# Sheet1_2.net
KiCad netlist of a schematic drawn in Altium Designer
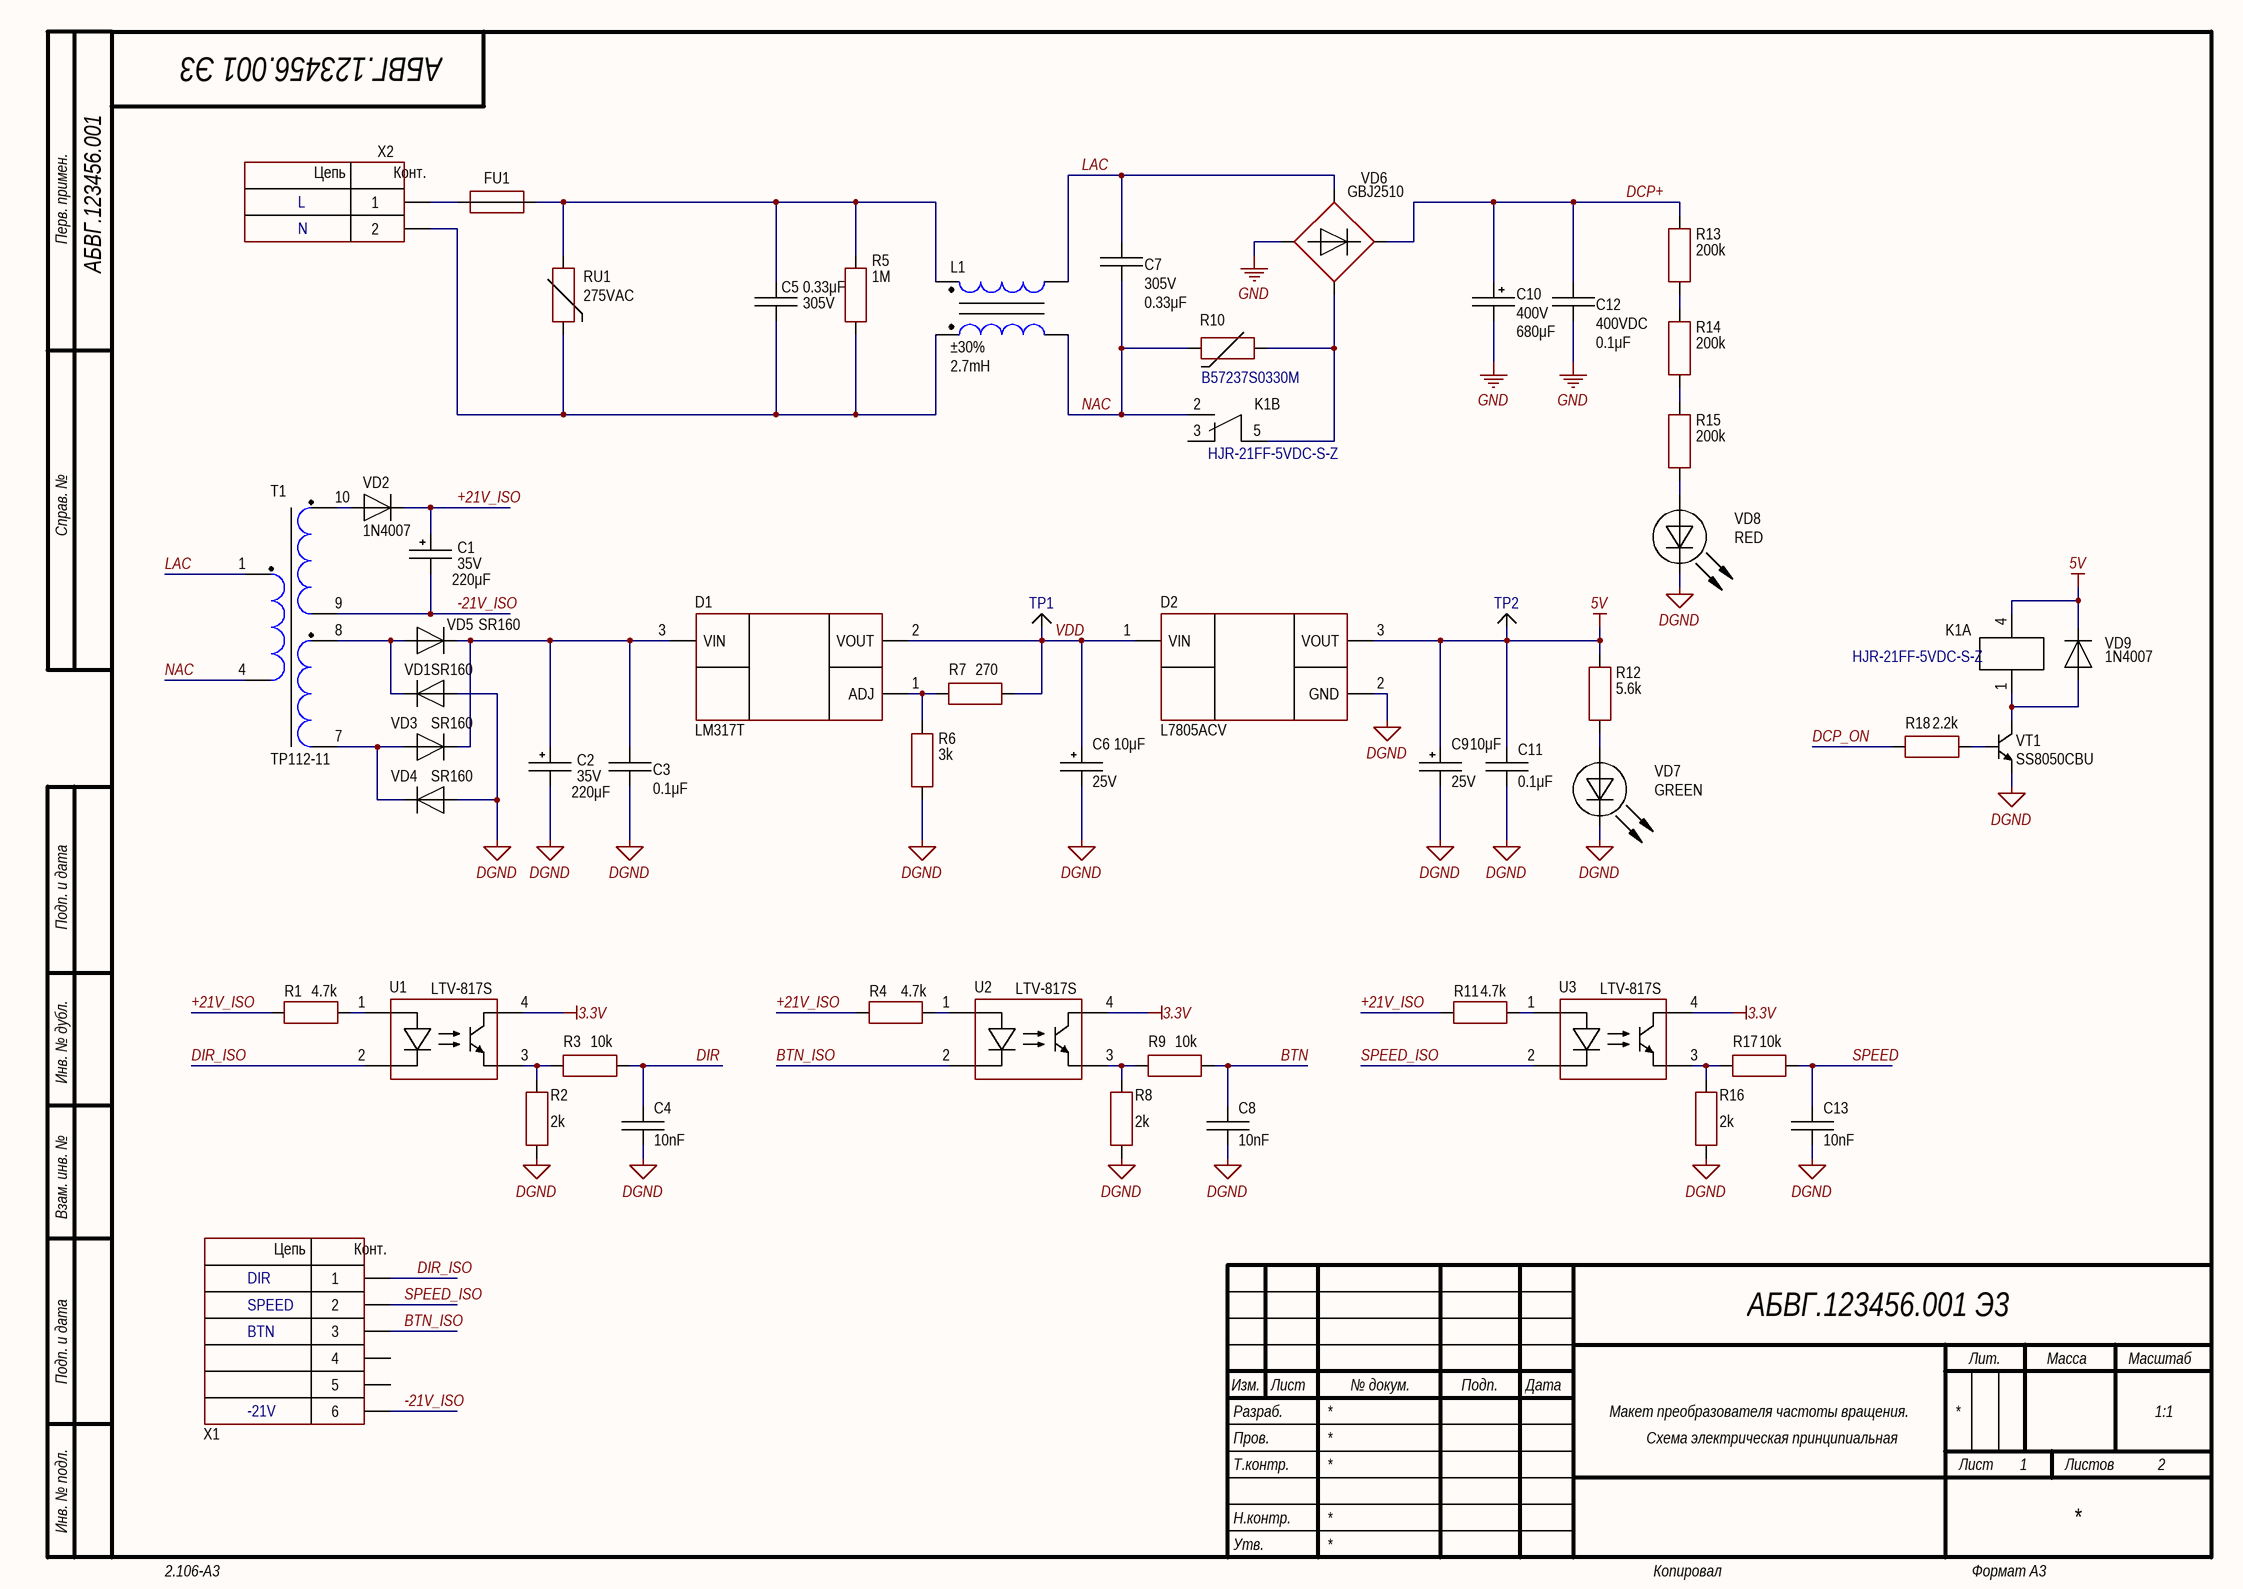
[diagram p0: Sheet1 (2).SchDoc]

(export (version "E")
  (design (tool "Eeschema 10.0.6"))
  (components
    (comp (ref "C1")
      (value "220μF")
      (footprint "CAP: D8C3.5H12")
      (fields
        (field (name "MANUFACTURER") "?")
        (field (name "PARTNUMBER") "9000565901")
        (field (name "VALUEMANUFACTURERPARTNUMBER") "Aluminium capacitor, 220μF, 35V, ±20%, 54mOhm, 8x12x3.5 mm, -40...+105°C")
        (field (name "VOLTAGE") "35V")
      )
      (libsource (lib "capacitor") (part "Aluminium"))
    )
    (comp (ref "C2")
      (value "220μF")
      (footprint "CAP: D8C3.5H12")
      (fields
        (field (name "MANUFACTURER") "?")
        (field (name "PARTNUMBER") "9000565901")
        (field (name "VALUEMANUFACTURERPARTNUMBER") "Aluminium capacitor, 220μF, 35V, ±20%, 54mOhm, 8x12x3.5 mm, -40...+105°C")
        (field (name "VOLTAGE") "35V")
      )
      (libsource (lib "capacitor") (part "Aluminium"))
    )
    (comp (ref "C3")
      (value "0.1μF")
      (footprint "CAP: 1206")
      (fields
        (field (name "PARTNUMBER") "Ceramic capacitor, 0.1μF,   50V")
        (field (name "VALUEMANUFACTURERPARTNUMBER") "Ceramic capacitor, 0.1μF, X7R, ±10%, 50V, 1206, -55...+125°C")
        (field (name "TOLERANCE") "±10%")
      )
      (libsource (lib "capacitor") (part "Ceramic_1206"))
    )
    (comp (ref "C4")
      (value "10nF")
      (footprint "CAP: 1206")
      (fields
        (field (name "PARTNUMBER") "Ceramic capacitor, 10nF,   50V")
        (field (name "VALUEMANUFACTURERPARTNUMBER") "Ceramic capacitor, 10nF, X7R, ±10%, 50V, 1206, -55...+125°C")
        (field (name "TOLERANCE") "±10%")
      )
      (libsource (lib "capacitor") (part "Ceramic_1206"))
    )
    (comp (ref "C5")
      (value "0.33μF")
      (footprint "CAP: B32922")
      (fields
        (field (name "MANUFACTURER") "Epcos")
        (field (name "PARTNUMBER") "B32922-C3334-K")
        (field (name "VALUEMANUFACTURERPARTNUMBER") "Film capacitor X2, 0.33μF, 305V, ±10%, ?, 18x14x8, -40...+110°C")
        (field (name "VOLTAGE") "305V")
      )
      (libsource (lib "capacitor") (part "Film"))
    )
    (comp (ref "C6")
      (value "10μF")
      (footprint "CAP: D5C2H11")
      (fields
        (field (name "MANUFACTURER") "?")
        (field (name "PARTNUMBER") "9000565842")
        (field (name "VALUEMANUFACTURERPARTNUMBER") "Aluminium capacitor, 10μF, 25V, ±20%, 54mOhm, ?, -40...+105°C")
        (field (name "VOLTAGE") "25V")
      )
      (libsource (lib "capacitor") (part "Aluminium"))
    )
    (comp (ref "C7")
      (value "0.33μF")
      (footprint "CAP: B32922")
      (fields
        (field (name "MANUFACTURER") "Epcos")
        (field (name "PARTNUMBER") "B32922-C3334-K")
        (field (name "VALUEMANUFACTURERPARTNUMBER") "Film capacitor X2, 0.33μF, 305V, ±10%, ?, 18x14x8, -40...+110°C")
        (field (name "VOLTAGE") "305V")
      )
      (libsource (lib "capacitor") (part "Film"))
    )
    (comp (ref "C8")
      (value "10nF")
      (footprint "CAP: 1206")
      (fields
        (field (name "PARTNUMBER") "Ceramic capacitor, 10nF,   50V")
        (field (name "VALUEMANUFACTURERPARTNUMBER") "Ceramic capacitor, 10nF, X7R, ±10%, 50V, 1206, -55...+125°C")
        (field (name "TOLERANCE") "±10%")
      )
      (libsource (lib "capacitor") (part "Ceramic_1206"))
    )
    (comp (ref "C9")
      (value "10μF")
      (footprint "CAP: D5C2H11")
      (fields
        (field (name "MANUFACTURER") "?")
        (field (name "PARTNUMBER") "9000565842")
        (field (name "VALUEMANUFACTURERPARTNUMBER") "Aluminium capacitor, 10μF, 25V, ±20%, 54mOhm, ?, -40...+105°C")
        (field (name "VOLTAGE") "25V")
      )
      (libsource (lib "capacitor") (part "Aluminium"))
    )
    (comp (ref "C10")
      (value "680μF")
      (footprint "CAP: D30C10H37")
      (fields
        (field (name "MANUFACTURER") "JB Capacitors")
        (field (name "PARTNUMBER") "JNE2G681M10003000600")
        (field (name "VALUEMANUFACTURERPARTNUMBER") "Aluminium capacitor, 680μF, 400V, ±20%, ?, 30x10x60 mm, -25...+105°C")
        (field (name "VOLTAGE") "400V")
      )
      (libsource (lib "capacitor") (part "Aluminium"))
    )
    (comp (ref "C11")
      (value "0.1μF")
      (footprint "CAP: 1206")
      (fields
        (field (name "PARTNUMBER") "Ceramic capacitor, 0.1μF,   50V")
        (field (name "VALUEMANUFACTURERPARTNUMBER") "Ceramic capacitor, 0.1μF, X7R, ±10%, 50V, 1206, -55...+125°C")
        (field (name "TOLERANCE") "±10%")
      )
      (libsource (lib "capacitor") (part "Ceramic_1206"))
    )
    (comp (ref "C12")
      (value "0.1μF")
      (footprint "CAP: B32673")
      (fields
        (field (name "MANUFACTURER") "Epcos")
        (field (name "PARTNUMBER") "B32683A4104J000")
        (field (name "VALUEMANUFACTURERPARTNUMBER") "Film capacitor, 0.1μF, 400VDC, ±10%, ?, 26.5x16.5x8.5 mm, -55...+100°C")
        (field (name "VOLTAGE") "400VDC")
      )
      (libsource (lib "capacitor") (part "Film"))
    )
    (comp (ref "C13")
      (value "10nF")
      (footprint "CAP: 1206")
      (fields
        (field (name "PARTNUMBER") "Ceramic capacitor, 10nF,   50V")
        (field (name "VALUEMANUFACTURERPARTNUMBER") "Ceramic capacitor, 10nF, X7R, ±10%, 50V, 1206, -55...+125°C")
        (field (name "TOLERANCE") "±10%")
      )
      (libsource (lib "capacitor") (part "Ceramic_1206"))
    )
    (comp (ref "D1")
      (value "~")
      (footprint "TO-220F")
      (description "Adjustable voltage regulator")
      (fields
        (field (name "MANUFACTURER") "STMicroelectronics")
        (field (name "VALUEMANUFACTURERPARTNUMBER") ", , , , , , , TO-220SG, 0...125°C")
        (field (name "PARTNUMBER") "LM317T")
      )
      (libsource (lib "ic-power-supply") (part "LM317"))
    )
    (comp (ref "D2")
      (value "~")
      (footprint "TO-220F")
      (description "Linear voltage regulator")
      (fields
        (field (name "MANUFACTURER") "STMicroelectronics")
        (field (name "VALUEMANUFACTURERPARTNUMBER") ", , , , , , , *, *")
        (field (name "PARTNUMBER") "L7805ACV")
      )
      (libsource (lib "ic-power-supply") (part "78XX"))
    )
    (comp (ref "FU1")
      (value "~")
      (footprint "FUSE: FH-101")
      (fields
        (field (name "MANUFACTURER") "Dragon City Industries")
        (field (name "PARTNUMBER") "FH-101")
        (field (name "VALUEMANUFACTURERPARTNUMBER") "*,  FH-101, *")
      )
      (libsource (lib "resistor") (part "FUSE"))
    )
    (comp (ref "K1")
      (value "Relay, Non Latching, SPDT , 10A , (250VAC , 110VDC)")
      (footprint "HJR-21FF-5VDC-S-Z")
      (fields (field (name "MANUFACTURER") "Tianbo") (field (name "PARTNUMBER") "HJR-21FF-5VDC-S-Z"))
      (libsource (lib "relay") (part "HJR-21FF-5VDC-S-Z"))
    )
    (comp (ref "L1")
      (value "2.7mH")
      (footprint "IND: B82723A")
      (fields
        (field (name "MANUFACTURER") "TDK (TDK-Lambda)")
        (field (name "PARTNUMBER") "B82723A2402N1")
        (field (name "VALUEMANUFACTURERPARTNUMBER") "Fixed inductor, 2.7mH, ±30%, B82723A, CuNi18Zn20, ")
        (field (name "TOLERANCE") "±30%")
      )
      (libsource (lib "inductor") (part "B82723A"))
    )
    (comp (ref "R1")
      (value "4.7k")
      (footprint "RES: 1206")
      (fields
        (field (name "MANUFACTURER") "Yageo")
        (field (name "PARTNUMBER") "RC1206JR-07100RL")
        (field (name "VALUEMANUFACTURERPARTNUMBER") "Resistor film, 4.7k, ±5%, 1206, 0.25W, -55...+125°C")
      )
      (libsource (lib "") (part "Resistor_1206_2"))
    )
    (comp (ref "R2")
      (value "2k")
      (footprint "RES: 1206")
      (fields
        (field (name "MANUFACTURER") "Yageo")
        (field (name "PARTNUMBER") "RC1206JR-07100RL")
        (field (name "VALUEMANUFACTURERPARTNUMBER") "Resistor film, 2k, ±5%, 1206, 0.25W, -55...+125°C")
      )
      (libsource (lib "resistor") (part "Resistor_1206"))
    )
    (comp (ref "R3")
      (value "10k")
      (footprint "RES: 1206")
      (fields
        (field (name "MANUFACTURER") "Yageo")
        (field (name "PARTNUMBER") "RC1206JR-07100RL")
        (field (name "VALUEMANUFACTURERPARTNUMBER") "Resistor film, 10k, ±5%, 1206, 0.25W, -55...+125°C")
      )
      (libsource (lib "") (part "Resistor_1206_1"))
    )
    (comp (ref "R4")
      (value "4.7k")
      (footprint "RES: 1206")
      (fields
        (field (name "MANUFACTURER") "Yageo")
        (field (name "PARTNUMBER") "RC1206JR-07100RL")
        (field (name "VALUEMANUFACTURERPARTNUMBER") "Resistor film, 4.7k, ±5%, 1206, 0.25W, -55...+125°C")
      )
      (libsource (lib "") (part "Resistor_1206_2"))
    )
    (comp (ref "R5")
      (value "1M")
      (footprint "RES: Axial 15mm")
      (fields (field (name "TOLERANCE") "±5%"))
      (libsource (lib "resistor") (part "Resistor_Axial"))
    )
    (comp (ref "R6")
      (value "3k")
      (footprint "RES: 1206")
      (fields
        (field (name "MANUFACTURER") "Yageo")
        (field (name "PARTNUMBER") "RC1206JR-07100RL")
        (field (name "VALUEMANUFACTURERPARTNUMBER") "Resistor film, 3k, ±5%, 1206, 0.25W, -55...+125°C")
      )
      (libsource (lib "resistor") (part "Resistor_1206"))
    )
    (comp (ref "R7")
      (value "270")
      (footprint "RES: 1206")
      (fields
        (field (name "MANUFACTURER") "Yageo")
        (field (name "PARTNUMBER") "RC1206JR-07100RL")
        (field (name "VALUEMANUFACTURERPARTNUMBER") "Resistor film, 270, ±5%, 1206, 0.25W, -55...+125°C")
      )
      (libsource (lib "") (part "Resistor_1206_2"))
    )
    (comp (ref "R8")
      (value "2k")
      (footprint "RES: 1206")
      (fields
        (field (name "MANUFACTURER") "Yageo")
        (field (name "PARTNUMBER") "RC1206JR-07100RL")
        (field (name "VALUEMANUFACTURERPARTNUMBER") "Resistor film, 2k, ±5%, 1206, 0.25W, -55...+125°C")
      )
      (libsource (lib "resistor") (part "Resistor_1206"))
    )
    (comp (ref "R9")
      (value "10k")
      (footprint "RES: 1206")
      (fields
        (field (name "MANUFACTURER") "Yageo")
        (field (name "PARTNUMBER") "RC1206JR-07100RL")
        (field (name "VALUEMANUFACTURERPARTNUMBER") "Resistor film, 10k, ±5%, 1206, 0.25W, -55...+125°C")
      )
      (libsource (lib "") (part "Resistor_1206_1"))
    )
    (comp (ref "R10")
      (value "~")
      (footprint "RES: B57237 (NTC)")
      (description "Maximum permissible capacitance 900uF")
      (fields
        (field (name "MANUFACTURER") "Epcos")
        (field (name "PARTNUMBER") "B57237S0330M")
        (field (name "VALUEMANUFACTURERPARTNUMBER") "NTC resistor, 33, ±20%, pitch 7.5mm, 2.5A, -55...+170°C")
      )
      (libsource (lib "resistor") (part "NTC"))
    )
    (comp (ref "R11")
      (value "4.7k")
      (footprint "RES: 1206")
      (fields
        (field (name "MANUFACTURER") "Yageo")
        (field (name "PARTNUMBER") "RC1206JR-07100RL")
        (field (name "VALUEMANUFACTURERPARTNUMBER") "Resistor film, 4.7k, ±5%, 1206, 0.25W, -55...+125°C")
      )
      (libsource (lib "") (part "Resistor_1206_2"))
    )
    (comp (ref "R12")
      (value "5.6k")
      (footprint "RES: 1206")
      (fields
        (field (name "MANUFACTURER") "Yageo")
        (field (name "PARTNUMBER") "RC1206JR-07100RL")
        (field (name "VALUEMANUFACTURERPARTNUMBER") "Resistor film, 5.6k, ±5%, 1206, 0.25W, -55...+125°C")
      )
      (libsource (lib "resistor") (part "Resistor_1206"))
    )
    (comp (ref "R13")
      (value "200k")
      (footprint "RES: 1206")
      (fields
        (field (name "MANUFACTURER") "Yageo")
        (field (name "PARTNUMBER") "RC1206JR-07100RL")
        (field (name "VALUEMANUFACTURERPARTNUMBER") "Resistor film, 200k, ±5%, 1206, 0.25W, -55...+125°C")
      )
      (libsource (lib "resistor") (part "Resistor_1206"))
    )
    (comp (ref "R14")
      (value "200k")
      (footprint "RES: 1206")
      (fields
        (field (name "MANUFACTURER") "Yageo")
        (field (name "PARTNUMBER") "RC1206JR-07100RL")
        (field (name "VALUEMANUFACTURERPARTNUMBER") "Resistor film, 200k, ±5%, 1206, 0.25W, -55...+125°C")
      )
      (libsource (lib "resistor") (part "Resistor_1206"))
    )
    (comp (ref "R15")
      (value "200k")
      (footprint "RES: 1206")
      (fields
        (field (name "MANUFACTURER") "Yageo")
        (field (name "PARTNUMBER") "RC1206JR-07100RL")
        (field (name "VALUEMANUFACTURERPARTNUMBER") "Resistor film, 200k, ±5%, 1206, 0.25W, -55...+125°C")
      )
      (libsource (lib "resistor") (part "Resistor_1206"))
    )
    (comp (ref "R16")
      (value "2k")
      (footprint "RES: 1206")
      (fields
        (field (name "MANUFACTURER") "Yageo")
        (field (name "PARTNUMBER") "RC1206JR-07100RL")
        (field (name "VALUEMANUFACTURERPARTNUMBER") "Resistor film, 2k, ±5%, 1206, 0.25W, -55...+125°C")
      )
      (libsource (lib "resistor") (part "Resistor_1206"))
    )
    (comp (ref "R17")
      (value "10k")
      (footprint "RES: 1206")
      (fields
        (field (name "MANUFACTURER") "Yageo")
        (field (name "PARTNUMBER") "RC1206JR-07100RL")
        (field (name "VALUEMANUFACTURERPARTNUMBER") "Resistor film, 10k, ±5%, 1206, 0.25W, -55...+125°C")
      )
      (libsource (lib "") (part "Resistor_1206_1"))
    )
    (comp (ref "R18")
      (value "2.2k")
      (footprint "RES: 1206")
      (fields
        (field (name "MANUFACTURER") "Yageo")
        (field (name "PARTNUMBER") "RC1206JR-07100RL")
        (field (name "VALUEMANUFACTURERPARTNUMBER") "Resistor film, 2.2k, ±5%, 1206, 0.25W, -55...+125°C")
      )
      (libsource (lib "") (part "Resistor_1206_2"))
    )
    (comp (ref "RU1")
      (value "~")
      (footprint "VARISTOR: B72214")
      (fields
        (field (name "MANUFACTURER") "EPCOS")
        (field (name "PARTNUMBER") "B72214-S 271-K101")
        (field (name "VALUEMANUFACTURERPARTNUMBER") "Varistor, 275VAC, pitch 7mm,  -40…85°C")
        (field (name "MAXVOLTAGE") "275VAC")
      )
      (libsource (lib "resistor") (part "Varistor"))
    )
    (comp (ref "T1")
      (value "~")
      (footprint "TRANS: TP-112")
      (fields
        (field (name "MANUFACTURER") "?")
        (field (name "VALUEMANUFACTURERPARTNUMBER") "Transformer, TP112-11")
        (field (name "PARTNUMBER") "TP112-11")
        (field (name "PACKAGE") "TP112-11")
      )
      (libsource (lib "transformer") (part "TP-112"))
    )
    (comp (ref "TP1")
      (value "Test_Point")
      (footprint "TEST POINT KEYSTONE")
      (libsource (lib "other") (part "Test_Point"))
    )
    (comp (ref "TP2")
      (value "Test_Point")
      (footprint "TEST POINT KEYSTONE")
      (libsource (lib "other") (part "Test_Point"))
    )
    (comp (ref "U1")
      (value "~")
      (footprint "4-SMD")
      (description "Optoisolator")
      (fields
        (field (name "MANUFACTURER") "Lite-On")
        (field (name "VALUEMANUFACTURERPARTNUMBER") "IC optoisolator, 4µs/3µs, 5000Vrms, 35V, -40...+125°C, 4-SMD")
        (field (name "PARTNUMBER") "LTV-817S")
      )
      (libsource (lib "optoisolator") (part "LTV-817"))
    )
    (comp (ref "U2")
      (value "~")
      (footprint "4-SMD")
      (description "Optoisolator")
      (fields
        (field (name "MANUFACTURER") "Lite-On")
        (field (name "VALUEMANUFACTURERPARTNUMBER") "IC optoisolator, 4µs/3µs, 5000Vrms, 35V, -40...+125°C, 4-SMD")
        (field (name "PARTNUMBER") "LTV-817S")
      )
      (libsource (lib "optoisolator") (part "LTV-817"))
    )
    (comp (ref "U3")
      (value "~")
      (footprint "4-SMD")
      (description "Optoisolator")
      (fields
        (field (name "MANUFACTURER") "Lite-On")
        (field (name "VALUEMANUFACTURERPARTNUMBER") "IC optoisolator, 4µs/3µs, 5000Vrms, 35V, -40...+125°C, 4-SMD")
        (field (name "PARTNUMBER") "LTV-817S")
      )
      (libsource (lib "optoisolator") (part "LTV-817"))
    )
    (comp (ref "VD1")
      (value "~")
      (footprint "DIODE: DO41")
      (fields
        (field (name "MANUFACTURER") "China")
        (field (name "VALUEMANUFACTURERPARTNUMBER") "Single diode, 60V, 1A, 700mV, ?, DO-41,  -65…+150°C")
        (field (name "VOLTAGE") "60V")
        (field (name "PARTNUMBER") "SR160")
      )
      (libsource (lib "diode") (part "Diode_single"))
    )
    (comp (ref "VD2")
      (value "~")
      (footprint "DIODE: DO41")
      (fields
        (field (name "MANUFACTURER") "Diotec Semiconductor")
        (field (name "VALUEMANUFACTURERPARTNUMBER") "Single diode, 1000V, 1A, 1.1V, , DO-41, -65...+175 C")
        (field (name "VOLTAGE") "1000V")
        (field (name "PARTNUMBER") "1N4007")
      )
      (libsource (lib "diode") (part "Diode_single"))
    )
    (comp (ref "VD3")
      (value "~")
      (footprint "DIODE: DO41")
      (fields
        (field (name "MANUFACTURER") "China")
        (field (name "VALUEMANUFACTURERPARTNUMBER") "Single diode, 60V, 1A, 700mV, ?, DO-41,  -65…+150°C")
        (field (name "VOLTAGE") "60V")
        (field (name "PARTNUMBER") "SR160")
      )
      (libsource (lib "diode") (part "Diode_single"))
    )
    (comp (ref "VD4")
      (value "~")
      (footprint "DIODE: DO41")
      (fields
        (field (name "MANUFACTURER") "China")
        (field (name "VALUEMANUFACTURERPARTNUMBER") "Single diode, 60V, 1A, 700mV, ?, DO-41,  -65…+150°C")
        (field (name "VOLTAGE") "60V")
        (field (name "PARTNUMBER") "SR160")
      )
      (libsource (lib "diode") (part "Diode_single"))
    )
    (comp (ref "VD5")
      (value "~")
      (footprint "DIODE: DO41")
      (fields
        (field (name "MANUFACTURER") "China")
        (field (name "VALUEMANUFACTURERPARTNUMBER") "Single diode, 60V, 1A, 700mV, ?, DO-41,  -65…+150°C")
        (field (name "VOLTAGE") "60V")
        (field (name "PARTNUMBER") "SR160")
      )
      (libsource (lib "diode") (part "Diode_single"))
    )
    (comp (ref "VD6")
      (value "~")
      (footprint "DIODE: GBJ FLAT")
      (fields
        (field (name "MANUFACTURER") "DIODES INC.")
        (field (name "VALUEMANUFACTURERPARTNUMBER") "Single phase rectifier, 1000V, 25A, 1.05V, GBJ, -56...+150°C")
        (field (name "VOLTAGE") "1000V")
        (field (name "PARTNUMBER") "GBJ2510")
      )
      (libsource (lib "diode") (part "GBJ2510"))
    )
    (comp (ref "VD7")
      (value "~")
      (footprint "LED: Axial 3MM GREEN")
      (fields
        (field (name "VALUEMANUFACTURERPARTNUMBER") "LED, Green, *, *, *, -55...+150°C")
        (field (name "PARTNUMBER") "Green Led")
        (field (name "COLOR") "GREEN")
      )
      (libsource (lib "diode") (part "LED_single"))
    )
    (comp (ref "VD8")
      (value "~")
      (footprint "LED: Axial 3MM RED")
      (fields
        (field (name "VALUEMANUFACTURERPARTNUMBER") "LED, RED, *, *, *, -55...+150°C")
        (field (name "PARTNUMBER") "Red Led")
        (field (name "COLOR") "RED")
      )
      (libsource (lib "diode") (part "LED_single"))
    )
    (comp (ref "VD9")
      (value "~")
      (footprint "DIODE: DO41")
      (fields
        (field (name "MANUFACTURER") "Diotec Semiconductor")
        (field (name "VALUEMANUFACTURERPARTNUMBER") "Single diode, 1000V, 1A, 1.1V, , DO-41, -65...+175 C")
        (field (name "VOLTAGE") "1000V")
        (field (name "PARTNUMBER") "1N4007")
      )
      (libsource (lib "diode") (part "Diode_single"))
    )
    (comp (ref "VT1")
      (value "~")
      (footprint "TO-92 - formed leads")
      (fields
        (field (name "MANUFACTURER") "ON Semiconductor")
        (field (name "VALUEMANUFACTURERPARTNUMBER") "NPN transistor, 40V, 1.5A, 190MHz, 1W, 0.5Vmax, 120...200, TO-92, 150°C")
        (field (name "PARTNUMBER") "SS8050CBU")
      )
      (libsource (lib "transistor") (part "SS8050CBU"))
    )
    (comp (ref "X1")
      (value "~")
      (footprint "CON: PLS-6")
      (fields
        (field (name "MANUFACTURER") "Connfly")
        (field (name "VALUEMANUFACTURERPARTNUMBER") "Connector, 6pin, 2.54mm, 500VAC, 3A")
        (field (name "PARTNUMBER") "PLS-6")
      )
      (libsource (lib "connector") (part "PLS-6"))
    )
    (comp (ref "X2")
      (value "~")
      (footprint "DG128-7.5-02P")
      (fields
        (field (name "MANUFACTURER") "KLS electronic co ltd")
        (field (name "VALUEMANUFACTURERPARTNUMBER") "Connector, 2pin, 9.53mm, 300VAC, 16A")
        (field (name "PARTNUMBER") "KLS2-128-7.50-02P-4S")
      )
      (libsource (lib "connector") (part "KLS2-128-7.50-02P-4S (DG128-7.5-02P)"))
    )
  )
  (nets
    (net (code "1") (name "/+21V_ISO") (class "Default")
      (node (ref "C1") (pin "1") (pinfunction "1_1") (pintype "passive"))
      (node (ref "R1") (pin "1") (pinfunction "1_1") (pintype "passive"))
      (node (ref "R11") (pin "1") (pinfunction "1_1") (pintype "passive"))
      (node (ref "R4") (pin "1") (pinfunction "1_1") (pintype "passive"))
      (node (ref "VD2") (pin "2") (pinfunction "2_2") (pintype "passive"))
    )
    (net (code "2") (name "/-21V_ISO") (class "Default")
      (node (ref "C1") (pin "2") (pinfunction "2_2") (pintype "passive"))
      (node (ref "T1") (pin "9") (pinfunction "9_9") (pintype "power_in"))
      (node (ref "X1") (pin "6") (pinfunction "6_6") (pintype "power_in"))
    )
    (net (code "3") (name "/BTN") (class "Default")
      (node (ref "C8") (pin "2") (pinfunction "2_2") (pintype "passive"))
      (node (ref "R9") (pin "1") (pinfunction "1_1") (pintype "passive"))
    )
    (net (code "4") (name "/BTN_ISO") (class "Default")
      (node (ref "U2") (pin "2") (pinfunction "C_2") (pintype "passive"))
      (node (ref "X1") (pin "3") (pinfunction "3_3") (pintype "power_in"))
    )
    (net (code "5") (name "/DCP+") (class "Default")
      (node (ref "C10") (pin "1") (pinfunction "1_1") (pintype "passive"))
      (node (ref "C12") (pin "1") (pinfunction "1_1") (pintype "passive"))
      (node (ref "R13") (pin "2") (pinfunction "2_2") (pintype "passive"))
      (node (ref "VD6") (pin "3") (pinfunction "3_3") (pintype "passive"))
    )
    (net (code "6") (name "/DCP_ON") (class "Default")
      (node (ref "R18") (pin "1") (pinfunction "1_1") (pintype "passive"))
    )
    (net (code "7") (name "/DIR") (class "Default")
      (node (ref "C4") (pin "2") (pinfunction "2_2") (pintype "passive"))
      (node (ref "R3") (pin "1") (pinfunction "1_1") (pintype "passive"))
    )
    (net (code "8") (name "/DIR_ISO") (class "Default")
      (node (ref "U1") (pin "2") (pinfunction "C_2") (pintype "passive"))
      (node (ref "X1") (pin "1") (pinfunction "1_1") (pintype "passive"))
    )
    (net (code "9") (name "/LAC") (class "Default")
      (node (ref "C7") (pin "1") (pinfunction "1_1") (pintype "passive"))
      (node (ref "L1") (pin "1") (pinfunction "1_1") (pintype "passive"))
      (node (ref "T1") (pin "1") (pinfunction "1_1") (pintype "power_in"))
      (node (ref "VD6") (pin "2") (pinfunction "2_2") (pintype "passive"))
    )
    (net (code "10") (name "/NAC") (class "Default")
      (node (ref "C7") (pin "2") (pinfunction "2_2") (pintype "passive"))
      (node (ref "K1") (pin "2") (pinfunction "2_2") (pintype "passive"))
      (node (ref "L1") (pin "4") (pinfunction "4_4") (pintype "passive"))
      (node (ref "R10") (pin "2") (pinfunction "2_2") (pintype "passive"))
      (node (ref "T1") (pin "4") (pinfunction "4_4") (pintype "power_in"))
    )
    (net (code "11") (name "/SPEED") (class "Default")
      (node (ref "C13") (pin "2") (pinfunction "2_2") (pintype "passive"))
      (node (ref "R17") (pin "1") (pinfunction "1_1") (pintype "passive"))
    )
    (net (code "12") (name "/SPEED_ISO") (class "Default")
      (node (ref "U3") (pin "2") (pinfunction "C_2") (pintype "passive"))
      (node (ref "X1") (pin "2") (pinfunction "2_2") (pintype "passive"))
    )
    (net (code "13") (name "/VDD") (class "Default")
      (node (ref "C6") (pin "1") (pinfunction "1_1") (pintype "passive"))
      (node (ref "D1") (pin "2") (pinfunction "VOUT_2") (pintype "passive"))
      (node (ref "D2") (pin "1") (pinfunction "VIN_1") (pintype "passive"))
      (node (ref "R7") (pin "2") (pinfunction "2_2") (pintype "passive"))
      (node (ref "TP1") (pin "1") (pinfunction "1_1") (pintype "passive"))
    )
    (net (code "14") (name "3.3V") (class "Default")
      (node (ref "U1") (pin "4") (pinfunction "C_4") (pintype "passive"))
      (node (ref "U2") (pin "4") (pinfunction "C_4") (pintype "passive"))
      (node (ref "U3") (pin "4") (pinfunction "C_4") (pintype "passive"))
    )
    (net (code "15") (name "5V") (class "Default")
      (node (ref "C11") (pin "2") (pinfunction "2_2") (pintype "passive"))
      (node (ref "C9") (pin "1") (pinfunction "1_1") (pintype "passive"))
      (node (ref "D2") (pin "3") (pinfunction "VOUT_3") (pintype "passive"))
      (node (ref "K1") (pin "4") (pinfunction "4_4") (pintype "passive"))
      (node (ref "R12") (pin "2") (pinfunction "2_2") (pintype "passive"))
      (node (ref "TP2") (pin "1") (pinfunction "1_1") (pintype "passive"))
      (node (ref "VD9") (pin "2") (pinfunction "2_2") (pintype "passive"))
    )
    (net (code "16") (name "DGND") (class "Default")
      (node (ref "C11") (pin "1") (pinfunction "1_1") (pintype "passive"))
      (node (ref "C13") (pin "1") (pinfunction "1_1") (pintype "passive"))
      (node (ref "C2") (pin "2") (pinfunction "2_2") (pintype "passive"))
      (node (ref "C3") (pin "1") (pinfunction "1_1") (pintype "passive"))
      (node (ref "C4") (pin "1") (pinfunction "1_1") (pintype "passive"))
      (node (ref "C6") (pin "2") (pinfunction "2_2") (pintype "passive"))
      (node (ref "C8") (pin "1") (pinfunction "1_1") (pintype "passive"))
      (node (ref "C9") (pin "2") (pinfunction "2_2") (pintype "passive"))
      (node (ref "D2") (pin "2") (pinfunction "GND_2") (pintype "passive"))
      (node (ref "R16") (pin "1") (pinfunction "1_1") (pintype "passive"))
      (node (ref "R2") (pin "1") (pinfunction "1_1") (pintype "passive"))
      (node (ref "R6") (pin "1") (pinfunction "1_1") (pintype "passive"))
      (node (ref "R8") (pin "1") (pinfunction "1_1") (pintype "passive"))
      (node (ref "VD1") (pin "1") (pinfunction "1_1") (pintype "passive"))
      (node (ref "VD4") (pin "1") (pinfunction "1_1") (pintype "passive"))
      (node (ref "VD7") (pin "2") (pinfunction "C_2") (pintype "passive"))
      (node (ref "VD8") (pin "2") (pinfunction "C_2") (pintype "passive"))
      (node (ref "VT1") (pin "1") (pinfunction "E_1") (pintype "passive"))
    )
    (net (code "17") (name "GND") (class "Default")
      (node (ref "C10") (pin "2") (pinfunction "2_2") (pintype "passive"))
      (node (ref "C12") (pin "2") (pinfunction "2_2") (pintype "passive"))
      (node (ref "VD6") (pin "1") (pinfunction "1_1") (pintype "passive"))
    )
    (net (code "18") (name "Net-(C5-Pad1)") (class "Default")
      (node (ref "C5") (pin "1") (pinfunction "1_1") (pintype "passive"))
      (node (ref "FU1") (pin "2") (pinfunction "2_2") (pintype "passive"))
      (node (ref "L1") (pin "2") (pinfunction "2_2") (pintype "passive"))
      (node (ref "R5") (pin "2") (pinfunction "2_2") (pintype "passive"))
      (node (ref "RU1") (pin "1") (pinfunction "1_1") (pintype "passive"))
    )
    (net (code "19") (name "Net-(C5-Pad2)") (class "Default")
      (node (ref "C5") (pin "2") (pinfunction "2_2") (pintype "passive"))
      (node (ref "L1") (pin "3") (pinfunction "3_3") (pintype "passive"))
      (node (ref "R5") (pin "1") (pinfunction "1_1") (pintype "passive"))
      (node (ref "RU1") (pin "2") (pinfunction "2_2") (pintype "passive"))
      (node (ref "X2") (pin "2") (pinfunction "2_2") (pintype "passive"))
    )
    (net (code "20") (name "Net-(D1-ADJ)") (class "Default")
      (node (ref "D1") (pin "1") (pinfunction "ADJ_1") (pintype "passive"))
      (node (ref "R6") (pin "2") (pinfunction "2_2") (pintype "passive"))
      (node (ref "R7") (pin "1") (pinfunction "1_1") (pintype "passive"))
    )
    (net (code "21") (name "Net-(D1-VIN)") (class "Default")
      (node (ref "C2") (pin "1") (pinfunction "1_1") (pintype "passive"))
      (node (ref "C3") (pin "2") (pinfunction "2_2") (pintype "passive"))
      (node (ref "D1") (pin "3") (pinfunction "VIN_3") (pintype "passive"))
      (node (ref "VD3") (pin "2") (pinfunction "2_2") (pintype "passive"))
      (node (ref "VD5") (pin "2") (pinfunction "2_2") (pintype "passive"))
    )
    (net (code "22") (name "Net-(FU1-Pad1)") (class "Default")
      (node (ref "FU1") (pin "1") (pinfunction "1_1") (pintype "passive"))
      (node (ref "X2") (pin "1") (pinfunction "1_1") (pintype "passive"))
    )
    (net (code "23") (name "Net-(K1-Pad5)") (class "Default")
      (node (ref "K1") (pin "5") (pinfunction "5_5") (pintype "passive"))
      (node (ref "R10") (pin "1") (pinfunction "1_1") (pintype "passive"))
      (node (ref "VD6") (pin "4") (pinfunction "4_4") (pintype "passive"))
    )
    (net (code "24") (name "Net-(R13-Pad1)") (class "Default")
      (node (ref "R13") (pin "1") (pinfunction "1_1") (pintype "passive"))
      (node (ref "R14") (pin "2") (pinfunction "2_2") (pintype "passive"))
    )
    (net (code "25") (name "Net-(R14-Pad1)") (class "Default")
      (node (ref "R14") (pin "1") (pinfunction "1_1") (pintype "passive"))
      (node (ref "R15") (pin "2") (pinfunction "2_2") (pintype "passive"))
    )
    (net (code "26") (name "Net-(T1-Pad7)") (class "Default")
      (node (ref "T1") (pin "7") (pinfunction "7_7") (pintype "power_in"))
      (node (ref "VD3") (pin "1") (pinfunction "1_1") (pintype "passive"))
      (node (ref "VD4") (pin "2") (pinfunction "2_2") (pintype "passive"))
    )
    (net (code "27") (name "Net-(T1-Pad8)") (class "Default")
      (node (ref "T1") (pin "8") (pinfunction "8_8") (pintype "power_in"))
      (node (ref "VD1") (pin "2") (pinfunction "2_2") (pintype "passive"))
      (node (ref "VD5") (pin "1") (pinfunction "1_1") (pintype "passive"))
    )
    (net (code "28") (name "Net-(T1-Pad10)") (class "Default")
      (node (ref "T1") (pin "10") (pinfunction "10_10") (pintype "power_in"))
      (node (ref "VD2") (pin "1") (pinfunction "1_1") (pintype "passive"))
    )
    (net (code "29") (name "Net-(U1-A)") (class "Default")
      (node (ref "R1") (pin "2") (pinfunction "2_2") (pintype "passive"))
      (node (ref "U1") (pin "1") (pinfunction "A_1") (pintype "passive"))
    )
    (net (code "30") (name "Net-(U1-E)") (class "Default")
      (node (ref "R2") (pin "2") (pinfunction "2_2") (pintype "passive"))
      (node (ref "R3") (pin "2") (pinfunction "2_2") (pintype "passive"))
      (node (ref "U1") (pin "3") (pinfunction "E_3") (pintype "passive"))
    )
    (net (code "31") (name "Net-(U2-A)") (class "Default")
      (node (ref "R4") (pin "2") (pinfunction "2_2") (pintype "passive"))
      (node (ref "U2") (pin "1") (pinfunction "A_1") (pintype "passive"))
    )
    (net (code "32") (name "Net-(U2-E)") (class "Default")
      (node (ref "R8") (pin "2") (pinfunction "2_2") (pintype "passive"))
      (node (ref "R9") (pin "2") (pinfunction "2_2") (pintype "passive"))
      (node (ref "U2") (pin "3") (pinfunction "E_3") (pintype "passive"))
    )
    (net (code "33") (name "Net-(U3-A)") (class "Default")
      (node (ref "R11") (pin "2") (pinfunction "2_2") (pintype "passive"))
      (node (ref "U3") (pin "1") (pinfunction "A_1") (pintype "passive"))
    )
    (net (code "34") (name "Net-(U3-E)") (class "Default")
      (node (ref "R16") (pin "2") (pinfunction "2_2") (pintype "passive"))
      (node (ref "R17") (pin "2") (pinfunction "2_2") (pintype "passive"))
      (node (ref "U3") (pin "3") (pinfunction "E_3") (pintype "passive"))
    )
    (net (code "35") (name "Net-(VD7-A)") (class "Default")
      (node (ref "R12") (pin "1") (pinfunction "1_1") (pintype "passive"))
      (node (ref "VD7") (pin "1") (pinfunction "A_1") (pintype "passive"))
    )
    (net (code "36") (name "Net-(VD8-A)") (class "Default")
      (node (ref "R15") (pin "1") (pinfunction "1_1") (pintype "passive"))
      (node (ref "VD8") (pin "1") (pinfunction "A_1") (pintype "passive"))
    )
    (net (code "37") (name "Net-(VT1-B)") (class "Default")
      (node (ref "R18") (pin "2") (pinfunction "2_2") (pintype "passive"))
      (node (ref "VT1") (pin "2") (pinfunction "B_2") (pintype "passive"))
    )
    (net (code "38") (name "Net-(VT1-C)") (class "Default")
      (node (ref "K1") (pin "1") (pinfunction "1_1") (pintype "passive"))
      (node (ref "VD9") (pin "1") (pinfunction "1_1") (pintype "passive"))
      (node (ref "VT1") (pin "3") (pinfunction "C_3") (pintype "passive"))
    )
    (net (code "39") (name "unconnected-(K1-Pad3)") (class "Default")
      (node (ref "K1") (pin "3") (pinfunction "3_3") (pintype "passive"))
    )
    (net (code "40") (name "unconnected-(X1-Pad4)") (class "Default")
      (node (ref "X1") (pin "4") (pinfunction "4_4") (pintype "power_in"))
    )
    (net (code "41") (name "unconnected-(X1-Pad5)") (class "Default")
      (node (ref "X1") (pin "5") (pinfunction "5_5") (pintype "power_in"))
    )
  )
)
